# STM32_microcontroller_Power.net
KiCad netlist of a schematic drawn in Altium Designer
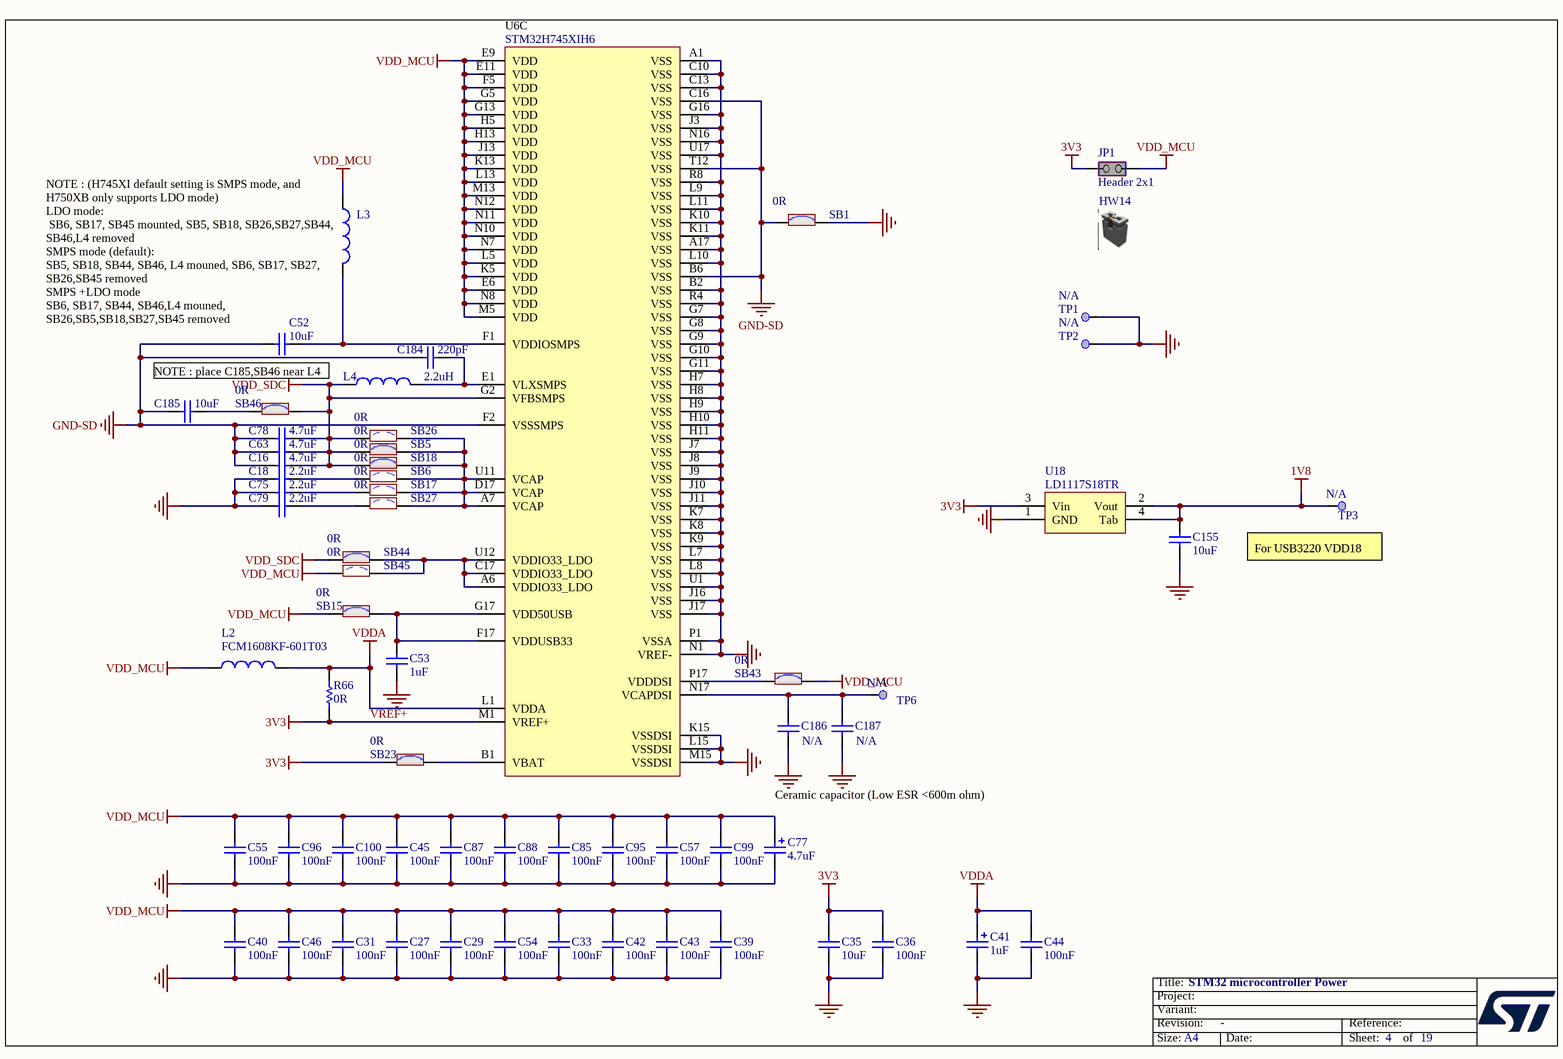
[diagram p0: STM32_microcontroller_Power.SchDoc]

(export (version "E")
  (design (tool "Eeschema 10.0.6"))
  (components
    (comp (ref "C16")
      (value "4.7uF")
      (footprint "C0402")
      (description "Capacitor, MLCC, 4.7uF, 6V3, X5R, 20%, 0402, T=0,5mm")
      (fields
        (field (name "INTERNAL_PART_NUMBER") "MCD-01356")
        (field (name "MANUFACTURER_PART_NUMBER") "GRM155R60J475ME47")
        (field (name "PROVIDED_BY") "Subcon")
      )
      (libsource (lib "MCD_PARTS_database") (part "Capacitor"))
    )
    (comp (ref "C18")
      (value "2.2uF")
      (footprint "C0603")
      (description "Capacitor, MLCC, 2.2uF, 10V, X5R, 10%, 0603, T=0,8mm")
      (fields
        (field (name "INTERNAL_PART_NUMBER") "MCD-00012")
        (field (name "MANUFACTURER_PART_NUMBER") "CC0603KRX5R6BB225")
        (field (name "PROVIDED_BY") "Subcon")
      )
      (libsource (lib "MCD_PARTS_database") (part "Capacitor"))
    )
    (comp (ref "C27")
      (value "100nF")
      (footprint "C0402")
      (description "Capacitor, MLCC, 100nF, 16V, X7R, +/-10%, 0402, T=0.5mm")
      (fields
        (field (name "INTERNAL_PART_NUMBER") "MCD-00006")
        (field (name "MANUFACTURER_PART_NUMBER") "CC0402KRX7R7BB104")
      )
      (libsource (lib "MCD_PARTS_database") (part "Capacitor"))
    )
    (comp (ref "C29")
      (value "100nF")
      (footprint "C0402")
      (description "Capacitor, MLCC, 100nF, 16V, X7R, +/-10%, 0402, T=0.5mm")
      (fields
        (field (name "INTERNAL_PART_NUMBER") "MCD-00006")
        (field (name "MANUFACTURER_PART_NUMBER") "CC0402KRX7R7BB104")
      )
      (libsource (lib "MCD_PARTS_database") (part "Capacitor"))
    )
    (comp (ref "C31")
      (value "100nF")
      (footprint "C0402")
      (description "Capacitor, MLCC, 100nF, 16V, X7R, +/-10%, 0402, T=0.5mm")
      (fields
        (field (name "INTERNAL_PART_NUMBER") "MCD-00006")
        (field (name "MANUFACTURER_PART_NUMBER") "CC0402KRX7R7BB104")
      )
      (libsource (lib "MCD_PARTS_database") (part "Capacitor"))
    )
    (comp (ref "C33")
      (value "100nF")
      (footprint "C0402")
      (description "Capacitor, MLCC, 100nF, 16V, X7R, +/-10%, 0402, T=0.5mm")
      (fields
        (field (name "INTERNAL_PART_NUMBER") "MCD-00006")
        (field (name "MANUFACTURER_PART_NUMBER") "CC0402KRX7R7BB104")
      )
      (libsource (lib "MCD_PARTS_database") (part "Capacitor"))
    )
    (comp (ref "C35")
      (value "10uF")
      (footprint "C0805")
      (description "Capacitor, MLCC, 10uF, 25V, X5R, 10%, 0805, T=0,85mm")
      (fields
        (field (name "INTERNAL_PART_NUMBER") "MCD-00014")
        (field (name "MANUFACTURER_PART_NUMBER") "CC0805KRX5R8BB106")
        (field (name "PROVIDED_BY") "Subcon")
      )
      (libsource (lib "MCD_PARTS_database") (part "Capacitor"))
    )
    (comp (ref "C36")
      (value "100nF")
      (footprint "C0402")
      (description "Capacitor, MLCC, 100nF, 16V, X7R, +/-10%, 0402, T=0.5mm")
      (fields
        (field (name "INTERNAL_PART_NUMBER") "MCD-00006")
        (field (name "MANUFACTURER_PART_NUMBER") "CC0402KRX7R7BB104")
      )
      (libsource (lib "MCD_PARTS_database") (part "Capacitor"))
    )
    (comp (ref "C39")
      (value "100nF")
      (footprint "C0402")
      (description "Capacitor, MLCC, 100nF, 16V, X7R, +/-10%, 0402, T=0.5mm")
      (fields
        (field (name "INTERNAL_PART_NUMBER") "MCD-00006")
        (field (name "MANUFACTURER_PART_NUMBER") "CC0402KRX7R7BB104")
      )
      (libsource (lib "MCD_PARTS_database") (part "Capacitor"))
    )
    (comp (ref "C40")
      (value "100nF")
      (footprint "C0402")
      (description "Capacitor, MLCC, 100nF, 16V, X7R, +/-10%, 0402, T=0.5mm")
      (fields
        (field (name "INTERNAL_PART_NUMBER") "MCD-00006")
        (field (name "MANUFACTURER_PART_NUMBER") "CC0402KRX7R7BB104")
      )
      (libsource (lib "MCD_PARTS_database") (part "Capacitor"))
    )
    (comp (ref "C41")
      (value "1uF")
      (footprint "CPOL_VISHAY_TANTAL-595D_1407_H220")
      (description "Capacitor, Tantalum, 1uF, 35V, +/-10%, 595D case A")
      (fields
        (field (name "INTERNAL_PART_NUMBER") "MCD-00594")
        (field (name "MANUFACTURER_PART_NUMBER") "595D105X9035A2T")
        (field (name "PROVIDED_BY") "Subcon")
      )
      (libsource (lib "MCD_PARTS_database") (part "Cap_POL_TANA"))
    )
    (comp (ref "C42")
      (value "100nF")
      (footprint "C0402")
      (description "Capacitor, MLCC, 100nF, 16V, X7R, +/-10%, 0402, T=0.5mm")
      (fields
        (field (name "INTERNAL_PART_NUMBER") "MCD-00006")
        (field (name "MANUFACTURER_PART_NUMBER") "CC0402KRX7R7BB104")
      )
      (libsource (lib "MCD_PARTS_database") (part "Capacitor"))
    )
    (comp (ref "C43")
      (value "100nF")
      (footprint "C0402")
      (description "Capacitor, MLCC, 100nF, 16V, X7R, +/-10%, 0402, T=0.5mm")
      (fields
        (field (name "INTERNAL_PART_NUMBER") "MCD-00006")
        (field (name "MANUFACTURER_PART_NUMBER") "CC0402KRX7R7BB104")
      )
      (libsource (lib "MCD_PARTS_database") (part "Capacitor"))
    )
    (comp (ref "C44")
      (value "100nF")
      (footprint "C0402")
      (description "Capacitor, MLCC, 100nF, 16V, X7R, +/-10%, 0402, T=0.5mm")
      (fields
        (field (name "INTERNAL_PART_NUMBER") "MCD-00006")
        (field (name "MANUFACTURER_PART_NUMBER") "CC0402KRX7R7BB104")
      )
      (libsource (lib "MCD_PARTS_database") (part "Capacitor"))
    )
    (comp (ref "C45")
      (value "100nF")
      (footprint "C0402")
      (description "Capacitor, MLCC, 100nF, 16V, X7R, +/-10%, 0402, T=0.5mm")
      (fields
        (field (name "INTERNAL_PART_NUMBER") "MCD-00006")
        (field (name "MANUFACTURER_PART_NUMBER") "CC0402KRX7R7BB104")
      )
      (libsource (lib "MCD_PARTS_database") (part "Capacitor"))
    )
    (comp (ref "C46")
      (value "100nF")
      (footprint "C0402")
      (description "Capacitor, MLCC, 100nF, 16V, X7R, +/-10%, 0402, T=0.5mm")
      (fields
        (field (name "INTERNAL_PART_NUMBER") "MCD-00006")
        (field (name "MANUFACTURER_PART_NUMBER") "CC0402KRX7R7BB104")
      )
      (libsource (lib "MCD_PARTS_database") (part "Capacitor"))
    )
    (comp (ref "C52")
      (value "10uF")
      (footprint "C0402")
      (description "Capacitor, MLCC, 10uF, 4V, X5R, 20%, 0402, T=0,5mm")
      (fields
        (field (name "INTERNAL_PART_NUMBER") "MCD-01355")
        (field (name "MANUFACTURER_PART_NUMBER") "GRM155R60G106ME44")
        (field (name "PROVIDED_BY") "Subcon")
      )
      (libsource (lib "MCD_PARTS_database") (part "Capacitor"))
    )
    (comp (ref "C53")
      (value "1uF")
      (footprint "C0603")
      (description "Capacitor, MLCC, 1uF, 16V, X5R, 10%, 0603, T=0,8mm")
      (fields
        (field (name "INTERNAL_PART_NUMBER") "MCD-00010")
        (field (name "MANUFACTURER_PART_NUMBER") "CC0603KRX5R7BB105")
        (field (name "PROVIDED_BY") "Subcon")
      )
      (libsource (lib "MCD_PARTS_database") (part "Capacitor"))
    )
    (comp (ref "C54")
      (value "100nF")
      (footprint "C0402")
      (description "Capacitor, MLCC, 100nF, 16V, X7R, +/-10%, 0402, T=0.5mm")
      (fields
        (field (name "INTERNAL_PART_NUMBER") "MCD-00006")
        (field (name "MANUFACTURER_PART_NUMBER") "CC0402KRX7R7BB104")
      )
      (libsource (lib "MCD_PARTS_database") (part "Capacitor"))
    )
    (comp (ref "C55")
      (value "100nF")
      (footprint "C0402")
      (description "Capacitor, MLCC, 100nF, 16V, X7R, +/-10%, 0402, T=0.5mm")
      (fields
        (field (name "INTERNAL_PART_NUMBER") "MCD-00006")
        (field (name "MANUFACTURER_PART_NUMBER") "CC0402KRX7R7BB104")
      )
      (libsource (lib "MCD_PARTS_database") (part "Capacitor"))
    )
    (comp (ref "C57")
      (value "100nF")
      (footprint "C0402")
      (description "Capacitor, MLCC, 100nF, 16V, X7R, +/-10%, 0402, T=0.5mm")
      (fields
        (field (name "INTERNAL_PART_NUMBER") "MCD-00006")
        (field (name "MANUFACTURER_PART_NUMBER") "CC0402KRX7R7BB104")
      )
      (libsource (lib "MCD_PARTS_database") (part "Capacitor"))
    )
    (comp (ref "C63")
      (value "4.7uF")
      (footprint "C0402")
      (description "Capacitor, MLCC, 4.7uF, 6V3, X5R, 20%, 0402, T=0,5mm")
      (fields
        (field (name "INTERNAL_PART_NUMBER") "MCD-01356")
        (field (name "MANUFACTURER_PART_NUMBER") "GRM155R60J475ME47")
        (field (name "PROVIDED_BY") "Subcon")
      )
      (libsource (lib "MCD_PARTS_database") (part "Capacitor"))
    )
    (comp (ref "C75")
      (value "2.2uF")
      (footprint "C0603")
      (description "Capacitor, MLCC, 2.2uF, 10V, X5R, 10%, 0603, T=0,8mm")
      (fields
        (field (name "INTERNAL_PART_NUMBER") "MCD-00012")
        (field (name "MANUFACTURER_PART_NUMBER") "CC0603KRX5R6BB225")
        (field (name "PROVIDED_BY") "Subcon")
      )
      (libsource (lib "MCD_PARTS_database") (part "Capacitor"))
    )
    (comp (ref "C77")
      (value "4.7uF")
      (footprint "CPOL_VISHAY_TANTAL-595D_1407_H220")
      (description "Capacitor, Tantalum, 4.7uF, 16V, +/-10%, 595D case A")
      (fields
        (field (name "INTERNAL_PART_NUMBER") "MCD-00595")
        (field (name "MANUFACTURER_PART_NUMBER") "595D475X9016A2T")
        (field (name "PROVIDED_BY") "Subcon")
      )
      (libsource (lib "MCD_PARTS_database") (part "Cap_POL_TANA"))
    )
    (comp (ref "C78")
      (value "4.7uF")
      (footprint "C0402")
      (description "Capacitor, MLCC, 4.7uF, 6V3, X5R, 20%, 0402, T=0,5mm")
      (fields
        (field (name "INTERNAL_PART_NUMBER") "MCD-01356")
        (field (name "MANUFACTURER_PART_NUMBER") "GRM155R60J475ME47")
        (field (name "PROVIDED_BY") "Subcon")
      )
      (libsource (lib "MCD_PARTS_database") (part "Capacitor"))
    )
    (comp (ref "C79")
      (value "2.2uF")
      (footprint "C0603")
      (description "Capacitor, MLCC, 2.2uF, 10V, X5R, 10%, 0603, T=0,8mm")
      (fields
        (field (name "INTERNAL_PART_NUMBER") "MCD-00012")
        (field (name "MANUFACTURER_PART_NUMBER") "CC0603KRX5R6BB225")
        (field (name "PROVIDED_BY") "Subcon")
      )
      (libsource (lib "MCD_PARTS_database") (part "Capacitor"))
    )
    (comp (ref "C85")
      (value "100nF")
      (footprint "C0402")
      (description "Capacitor, MLCC, 100nF, 16V, X7R, +/-10%, 0402, T=0.5mm")
      (fields
        (field (name "INTERNAL_PART_NUMBER") "MCD-00006")
        (field (name "MANUFACTURER_PART_NUMBER") "CC0402KRX7R7BB104")
      )
      (libsource (lib "MCD_PARTS_database") (part "Capacitor"))
    )
    (comp (ref "C87")
      (value "100nF")
      (footprint "C0402")
      (description "Capacitor, MLCC, 100nF, 16V, X7R, +/-10%, 0402, T=0.5mm")
      (fields
        (field (name "INTERNAL_PART_NUMBER") "MCD-00006")
        (field (name "MANUFACTURER_PART_NUMBER") "CC0402KRX7R7BB104")
      )
      (libsource (lib "MCD_PARTS_database") (part "Capacitor"))
    )
    (comp (ref "C88")
      (value "100nF")
      (footprint "C0402")
      (description "Capacitor, MLCC, 100nF, 16V, X7R, +/-10%, 0402, T=0.5mm")
      (fields
        (field (name "INTERNAL_PART_NUMBER") "MCD-00006")
        (field (name "MANUFACTURER_PART_NUMBER") "CC0402KRX7R7BB104")
      )
      (libsource (lib "MCD_PARTS_database") (part "Capacitor"))
    )
    (comp (ref "C95")
      (value "100nF")
      (footprint "C0402")
      (description "Capacitor, MLCC, 100nF, 16V, X7R, +/-10%, 0402, T=0.5mm")
      (fields
        (field (name "INTERNAL_PART_NUMBER") "MCD-00006")
        (field (name "MANUFACTURER_PART_NUMBER") "CC0402KRX7R7BB104")
      )
      (libsource (lib "MCD_PARTS_database") (part "Capacitor"))
    )
    (comp (ref "C96")
      (value "100nF")
      (footprint "C0402")
      (description "Capacitor, MLCC, 100nF, 16V, X7R, +/-10%, 0402, T=0.5mm")
      (fields
        (field (name "INTERNAL_PART_NUMBER") "MCD-00006")
        (field (name "MANUFACTURER_PART_NUMBER") "CC0402KRX7R7BB104")
      )
      (libsource (lib "MCD_PARTS_database") (part "Capacitor"))
    )
    (comp (ref "C99")
      (value "100nF")
      (footprint "C0402")
      (description "Capacitor, MLCC, 100nF, 16V, X7R, +/-10%, 0402, T=0.5mm")
      (fields
        (field (name "INTERNAL_PART_NUMBER") "MCD-00006")
        (field (name "MANUFACTURER_PART_NUMBER") "CC0402KRX7R7BB104")
      )
      (libsource (lib "MCD_PARTS_database") (part "Capacitor"))
    )
    (comp (ref "C100")
      (value "100nF")
      (footprint "C0402")
      (description "Capacitor, MLCC, 100nF, 16V, X7R, +/-10%, 0402, T=0.5mm")
      (fields
        (field (name "INTERNAL_PART_NUMBER") "MCD-00006")
        (field (name "MANUFACTURER_PART_NUMBER") "CC0402KRX7R7BB104")
      )
      (libsource (lib "MCD_PARTS_database") (part "Capacitor"))
    )
    (comp (ref "C155")
      (value "10uF")
      (footprint "C0805")
      (description "Capacitor, MLCC, 10uF, 25V, X5R, 10%, 0805, T=0,85mm")
      (fields
        (field (name "INTERNAL_PART_NUMBER") "MCD-00014")
        (field (name "MANUFACTURER_PART_NUMBER") "CC0805KRX5R8BB106")
        (field (name "PROVIDED_BY") "Subcon")
      )
      (libsource (lib "MCD_PARTS_database") (part "Capacitor"))
    )
    (comp (ref "C184")
      (value "220pF")
      (footprint "C0402")
      (description "Capacitor, MLCC, 220pF, 50V, NPO, 5%, 0402, T=0,5mm")
      (fields
        (field (name "INTERNAL_PART_NUMBER") "MCD-01225")
        (field (name "MANUFACTURER_PART_NUMBER") "CC0402JRNPO9BN221")
        (field (name "PROVIDED_BY") "Subcon")
      )
      (libsource (lib "MCD_PARTS_database") (part "Capacitor"))
    )
    (comp (ref "C185")
      (value "10uF")
      (footprint "C0603")
      (description "Capacitor, MLCC, 10uF, 6V3, X5R, 20%, 0603, T=0,8mm")
      (fields
        (field (name "INTERNAL_PART_NUMBER") "MCD-01341")
        (field (name "MANUFACTURER_PART_NUMBER") "GRM188R60J106ME47D")
        (field (name "PROVIDED_BY") "Subcon")
      )
      (libsource (lib "MCD_PARTS_database") (part "Capacitor"))
    )
    (comp (ref "C186")
      (value "N/A")
      (footprint "C0603")
      (description "Capacitor, MLCC, 2.2uF, 10V, X5R, 10%, 0603, T=0,8mm")
      (fields
        (field (name "INTERNAL_PART_NUMBER") "MCD-00012")
        (field (name "MANUFACTURER_PART_NUMBER") "CC0603KRX5R6BB225")
        (field (name "PROVIDED_BY") "Subcon")
      )
      (libsource (lib "MCD_PARTS_database") (part "Capacitor"))
    )
    (comp (ref "C187")
      (value "N/A")
      (footprint "C0402")
      (description "Capacitor, MLCC, 100nF, 16V, X7R, +/-10%, 0402, T=0.5mm")
      (fields
        (field (name "INTERNAL_PART_NUMBER") "MCD-00006")
        (field (name "MANUFACTURER_PART_NUMBER") "CC0402KRX7R7BB104")
      )
      (libsource (lib "MCD_PARTS_database") (part "Capacitor"))
    )
    (comp (ref "HW14")
      (value "Shunt 2.54mm")
      (footprint "N/A")
      (description "SHUNT 2.54mm BLACK")
      (fields
        (field (name "INTERNAL_PART_NUMBER") "MCD-00043")
        (field (name "MANUFACTURER_PART_NUMBER") "SNT-100-BK-G")
        (field (name "PROVIDED_BY") "Subcon")
      )
      (libsource (lib "MCD_PARTS_database") (part "Shunt 2.54mm"))
    )
    (comp (ref "JP1")
      (value "Header 2x1")
      (footprint "CON_SAMTEC_TSW-102-07-G-S")
      (description "Header, 2x1, 2.54mm, VR, TH, T=5.84mm/2.54mm")
      (fields
        (field (name "INTERNAL_PART_NUMBER") "MCD-00683")
        (field (name "MANUFACTURER_PART_NUMBER") "TSW-102-07-G-S")
      )
      (libsource (lib "MCD_PARTS_database") (part "Jumper_Header 2x1 Fitted"))
    )
    (comp (ref "L2")
      (value "BEAD")
      (footprint "L0603")
      (description "Ferrite bead, 600R @1 00MHz, +/-25%, 350mA, 0R5, 0603, T=0.8mm")
      (fields
        (field (name "INTERNAL_PART_NUMBER") "MCD-00047")
        (field (name "MANUFACTURER_PART_NUMBER") "FCM1608KF-601T03")
        (field (name "MANUFACTURER") "TAI-TECH")
      )
      (libsource (lib "MCD_PARTS_database") (part "BEAD"))
    )
    (comp (ref "L3")
      (value "Inductor")
      (footprint "IND_TAIYO-YUDEN_FBMJ1608")
      (description "Ferrite bead, 18R @ 100MHz, +/-30%, 750mA, 0R004, 0603, T=1mm")
      (fields
        (field (name "INTERNAL_PART_NUMBER") "MCD-01431")
        (field (name "MANUFACTURER_PART_NUMBER") "FBMJ1608HM180NTR")
      )
      (libsource (lib "MCD_PARTS_database") (part "Inductor"))
    )
    (comp (ref "L4")
      (value "2.2uH")
      (footprint "IND_2016_MURATA_LQM2MPN2R2NG0")
      (description "Inductor 2.2uH, 2x1.6x0.9mm")
      (fields
        (field (name "INTERNAL_PART_NUMBER") "MCD-01110")
        (field (name "MANUFACTURER_PART_NUMBER") "LQM2MPN2R2NG0")
        (field (name "PROVIDED_BY") "Subcon")
      )
      (libsource (lib "MCD_PARTS_database") (part "Inductor"))
    )
    (comp (ref "R66")
      (value "0R")
      (footprint "R0603")
      (description "Resistor,0R,0603,ULO")
      (fields
        (field (name "INTERNAL_PART_NUMBER") "MCD-00181")
        (field (name "MANUFACTURER_PART_NUMBER") "PMR03EZPJ000")
        (field (name "PROVIDED_BY") "Subcon")
      )
      (libsource (lib "MCD_PARTS_database") (part "Resistor"))
    )
    (comp (ref "SB1")
      (value "0R")
      (footprint "SOLDER-BRIDGE_R0603-0R")
      (description "Solder Bridge ON")
      (fields
        (field (name "INTERNAL_PART_NUMBER") "MCD-00071")
        (field (name "MANUFACTURER") "YAGEO")
        (field (name "PROVIDED_BY") "Subcon")
      )
      (libsource (lib "MCD_PARTS_database") (part "SB_ON"))
    )
    (comp (ref "SB5")
      (value "0R")
      (footprint "SOLDER-BRIDGE_R0603-0R")
      (description "Solder Bridge ON")
      (fields
        (field (name "INTERNAL_PART_NUMBER") "MCD-00071")
        (field (name "MANUFACTURER") "YAGEO")
        (field (name "PROVIDED_BY") "Subcon")
      )
      (libsource (lib "MCD_PARTS_database") (part "SB_ON"))
    )
    (comp (ref "SB6")
      (value "0R")
      (footprint "SOLDER-BRIDGE_R0603-0R")
      (description "Solder Bridge OFF")
      (fields (field (name "INTERNAL_PART_NUMBER") "MCD-00072") (field (name "MANUFACTURER") "YAGEO"))
      (libsource (lib "MCD_PARTS_database") (part "SB_OFF"))
    )
    (comp (ref "SB15")
      (value "0R")
      (footprint "SOLDER-BRIDGE_R0603-0R")
      (description "Solder Bridge ON")
      (fields
        (field (name "INTERNAL_PART_NUMBER") "MCD-00071")
        (field (name "MANUFACTURER") "YAGEO")
        (field (name "PROVIDED_BY") "Subcon")
      )
      (libsource (lib "MCD_PARTS_database") (part "SB_ON"))
    )
    (comp (ref "SB17")
      (value "0R")
      (footprint "SOLDER-BRIDGE_R0603-0R")
      (description "Solder Bridge OFF")
      (fields (field (name "INTERNAL_PART_NUMBER") "MCD-00072") (field (name "MANUFACTURER") "YAGEO"))
      (libsource (lib "MCD_PARTS_database") (part "SB_OFF"))
    )
    (comp (ref "SB18")
      (value "0R")
      (footprint "SOLDER-BRIDGE_R0603-0R")
      (description "Solder Bridge ON")
      (fields
        (field (name "INTERNAL_PART_NUMBER") "MCD-00071")
        (field (name "MANUFACTURER") "YAGEO")
        (field (name "PROVIDED_BY") "Subcon")
      )
      (libsource (lib "MCD_PARTS_database") (part "SB_ON"))
    )
    (comp (ref "SB23")
      (value "0R")
      (footprint "SOLDER-BRIDGE_R0603-0R")
      (description "Solder Bridge ON")
      (fields
        (field (name "INTERNAL_PART_NUMBER") "MCD-00071")
        (field (name "MANUFACTURER") "YAGEO")
        (field (name "PROVIDED_BY") "Subcon")
      )
      (libsource (lib "MCD_PARTS_database") (part "SB_ON"))
    )
    (comp (ref "SB26")
      (value "0R")
      (footprint "SOLDER-BRIDGE_R0603-0R")
      (description "Solder Bridge OFF")
      (fields (field (name "INTERNAL_PART_NUMBER") "MCD-00072") (field (name "MANUFACTURER") "YAGEO"))
      (libsource (lib "MCD_PARTS_database") (part "SB_OFF"))
    )
    (comp (ref "SB27")
      (value "0R")
      (footprint "SOLDER-BRIDGE_R0603-0R")
      (description "Solder Bridge OFF")
      (fields (field (name "INTERNAL_PART_NUMBER") "MCD-00072") (field (name "MANUFACTURER") "YAGEO"))
      (libsource (lib "MCD_PARTS_database") (part "SB_OFF"))
    )
    (comp (ref "SB43")
      (value "0R")
      (footprint "SOLDER-BRIDGE_R0603-0R")
      (description "Solder Bridge ON")
      (fields
        (field (name "INTERNAL_PART_NUMBER") "MCD-00071")
        (field (name "MANUFACTURER") "YAGEO")
        (field (name "PROVIDED_BY") "Subcon")
      )
      (libsource (lib "MCD_PARTS_database") (part "SB_ON"))
    )
    (comp (ref "SB44")
      (value "0R")
      (footprint "SOLDER-BRIDGE_R0603-0R")
      (description "Solder Bridge ON")
      (fields
        (field (name "INTERNAL_PART_NUMBER") "MCD-00071")
        (field (name "MANUFACTURER") "YAGEO")
        (field (name "PROVIDED_BY") "Subcon")
      )
      (libsource (lib "MCD_PARTS_database") (part "SB_ON"))
    )
    (comp (ref "SB45")
      (value "0R")
      (footprint "SOLDER-BRIDGE_R0603-0R")
      (description "Solder Bridge OFF")
      (fields (field (name "INTERNAL_PART_NUMBER") "MCD-00072") (field (name "MANUFACTURER") "YAGEO"))
      (libsource (lib "MCD_PARTS_database") (part "SB_OFF"))
    )
    (comp (ref "SB46")
      (value "0R")
      (footprint "SOLDER-BRIDGE_R0603-0R")
      (description "Solder Bridge ON")
      (fields
        (field (name "INTERNAL_PART_NUMBER") "MCD-00071")
        (field (name "MANUFACTURER") "YAGEO")
        (field (name "PROVIDED_BY") "Subcon")
      )
      (libsource (lib "MCD_PARTS_database") (part "SB_ON"))
    )
    (comp (ref "TP1")
      (value "N/A")
      (footprint "TP_SMD_0-3MM")
      (description "Test Point 0.3mm")
      (fields (field (name "INTERNAL_PART_NUMBER") "MCD-00630") (field (name "Comment") "Test Point"))
      (libsource (lib "MCD_PARTS_database") (part "Test Point"))
    )
    (comp (ref "TP2")
      (value "N/A")
      (footprint "TP_SMD_0-3MM")
      (description "Test Point 0.3mm")
      (fields (field (name "INTERNAL_PART_NUMBER") "MCD-00630") (field (name "Comment") "Test Point"))
      (libsource (lib "MCD_PARTS_database") (part "Test Point"))
    )
    (comp (ref "TP3")
      (value "N/A")
      (footprint "TP_SMD_0-3MM")
      (description "Test Point 0.3mm")
      (fields (field (name "INTERNAL_PART_NUMBER") "MCD-00630") (field (name "Comment") "Test Point"))
      (libsource (lib "") (part "Test Point_1"))
    )
    (comp (ref "TP6")
      (value "N/A")
      (footprint "TP_SMD_0-3MM")
      (description "Test Point 0.3mm")
      (fields (field (name "INTERNAL_PART_NUMBER") "MCD-00630") (field (name "Comment") "Test Point"))
      (libsource (lib "") (part "Test Point_1"))
    )
    (comp (ref "U6")
      (value "STM32H745XIH6")
      (footprint "ICC_TFBGA240+25_14X14_STM32H745H6U_P080")
      (description "32bit MCU TFBGA240+25")
      (fields
        (field (name "INTERNAL_PART_NUMBER") "MCD-01085")
        (field (name "MANUFACTURER") "STMICROELECTRONICS")
        (field (name "PROVIDED_BY") "STM")
      )
      (libsource (lib "MCD_PARTS_database") (part "STM32H745XIH6"))
    )
    (comp (ref "U18")
      (value "LD1117S18TR")
      (footprint "REG_SOT223-TAB")
      (description "Adjustable and fixed low drop positive voltage regulator")
      (fields
        (field (name "INTERNAL_PART_NUMBER") "MCD-01070")
        (field (name "MANUFACTURER") "STMICROELECTRONICS")
        (field (name "PROVIDED_BY") "Subcon")
      )
      (libsource (lib "MCD_PARTS_database") (part "LD1117S18TR"))
    )
  )
  (nets
    (net (code "1") (name "1V8") (class "Default")
      (node (ref "C155") (pin "2") (pinfunction "2_2") (pintype "passive"))
      (node (ref "TP3") (pin "1") (pinfunction "1_1") (pintype "passive"))
      (node (ref "U18") (pin "2") (pinfunction "Vout_2") (pintype "power_in"))
      (node (ref "U18") (pin "4") (pinfunction "Tab_4") (pintype "power_in"))
    )
    (net (code "2") (name "3V3") (class "Default")
      (node (ref "C35") (pin "2") (pinfunction "2_2") (pintype "passive"))
      (node (ref "C36") (pin "2") (pinfunction "2_2") (pintype "passive"))
      (node (ref "JP1") (pin "2") (pinfunction "NO_2") (pintype "passive"))
      (node (ref "R66") (pin "2") (pinfunction "2_2") (pintype "passive"))
      (node (ref "SB23") (pin "1") (pinfunction "1_1") (pintype "passive"))
      (node (ref "U18") (pin "3") (pinfunction "Vin_3") (pintype "power_in"))
      (node (ref "U6") (pin "M1") (pinfunction "VREF+_M1") (pintype "passive"))
    )
    (net (code "3") (name "GND") (class "Default")
      (node (ref "C100") (pin "1") (pinfunction "1_1") (pintype "passive"))
      (node (ref "C155") (pin "1") (pinfunction "1_1") (pintype "passive"))
      (node (ref "C18") (pin "1") (pinfunction "1_1") (pintype "passive"))
      (node (ref "C186") (pin "1") (pinfunction "1_1") (pintype "passive"))
      (node (ref "C187") (pin "1") (pinfunction "1_1") (pintype "passive"))
      (node (ref "C27") (pin "1") (pinfunction "1_1") (pintype "passive"))
      (node (ref "C29") (pin "1") (pinfunction "1_1") (pintype "passive"))
      (node (ref "C31") (pin "1") (pinfunction "1_1") (pintype "passive"))
      (node (ref "C33") (pin "1") (pinfunction "1_1") (pintype "passive"))
      (node (ref "C35") (pin "1") (pinfunction "1_1") (pintype "passive"))
      (node (ref "C36") (pin "1") (pinfunction "1_1") (pintype "passive"))
      (node (ref "C39") (pin "1") (pinfunction "1_1") (pintype "passive"))
      (node (ref "C40") (pin "1") (pinfunction "1_1") (pintype "passive"))
      (node (ref "C41") (pin "2") (pinfunction "2_2") (pintype "passive"))
      (node (ref "C42") (pin "1") (pinfunction "1_1") (pintype "passive"))
      (node (ref "C43") (pin "1") (pinfunction "1_1") (pintype "passive"))
      (node (ref "C44") (pin "1") (pinfunction "1_1") (pintype "passive"))
      (node (ref "C45") (pin "1") (pinfunction "1_1") (pintype "passive"))
      (node (ref "C46") (pin "1") (pinfunction "1_1") (pintype "passive"))
      (node (ref "C53") (pin "1") (pinfunction "1_1") (pintype "passive"))
      (node (ref "C54") (pin "1") (pinfunction "1_1") (pintype "passive"))
      (node (ref "C55") (pin "1") (pinfunction "1_1") (pintype "passive"))
      (node (ref "C57") (pin "1") (pinfunction "1_1") (pintype "passive"))
      (node (ref "C75") (pin "1") (pinfunction "1_1") (pintype "passive"))
      (node (ref "C77") (pin "2") (pinfunction "2_2") (pintype "passive"))
      (node (ref "C79") (pin "1") (pinfunction "1_1") (pintype "passive"))
      (node (ref "C85") (pin "1") (pinfunction "1_1") (pintype "passive"))
      (node (ref "C87") (pin "1") (pinfunction "1_1") (pintype "passive"))
      (node (ref "C88") (pin "1") (pinfunction "1_1") (pintype "passive"))
      (node (ref "C95") (pin "1") (pinfunction "1_1") (pintype "passive"))
      (node (ref "C96") (pin "1") (pinfunction "1_1") (pintype "passive"))
      (node (ref "C99") (pin "1") (pinfunction "1_1") (pintype "passive"))
      (node (ref "SB1") (pin "2") (pinfunction "2_2") (pintype "passive"))
      (node (ref "TP1") (pin "1") (pinfunction "1_1") (pintype "passive"))
      (node (ref "TP2") (pin "1") (pinfunction "1_1") (pintype "passive"))
      (node (ref "U18") (pin "1") (pinfunction "GND_1") (pintype "power_in"))
      (node (ref "U6") (pin "A1") (pinfunction "VSS_A1") (pintype "passive"))
      (node (ref "U6") (pin "A17") (pinfunction "VSS_A17") (pintype "passive"))
      (node (ref "U6") (pin "B2") (pinfunction "VSS_B2") (pintype "passive"))
      (node (ref "U6") (pin "C10") (pinfunction "VSS_C10") (pintype "passive"))
      (node (ref "U6") (pin "C13") (pinfunction "VSS_C13") (pintype "passive"))
      (node (ref "U6") (pin "G10") (pinfunction "VSS_G10") (pintype "passive"))
      (node (ref "U6") (pin "G11") (pinfunction "VSS_G11") (pintype "passive"))
      (node (ref "U6") (pin "G16") (pinfunction "VSS_G16") (pintype "passive"))
      (node (ref "U6") (pin "G7") (pinfunction "VSS_G7") (pintype "passive"))
      (node (ref "U6") (pin "G8") (pinfunction "VSS_G8") (pintype "passive"))
      (node (ref "U6") (pin "G9") (pinfunction "VSS_G9") (pintype "passive"))
      (node (ref "U6") (pin "H10") (pinfunction "VSS_H10") (pintype "passive"))
      (node (ref "U6") (pin "H11") (pinfunction "VSS_H11") (pintype "passive"))
      (node (ref "U6") (pin "H7") (pinfunction "VSS_H7") (pintype "passive"))
      (node (ref "U6") (pin "H8") (pinfunction "VSS_H8") (pintype "passive"))
      (node (ref "U6") (pin "H9") (pinfunction "VSS_H9") (pintype "passive"))
      (node (ref "U6") (pin "J10") (pinfunction "VSS_J10") (pintype "passive"))
      (node (ref "U6") (pin "J11") (pinfunction "VSS_J11") (pintype "passive"))
      (node (ref "U6") (pin "J16") (pinfunction "VSS_J16") (pintype "passive"))
      (node (ref "U6") (pin "J17") (pinfunction "VSS_J17") (pintype "passive"))
      (node (ref "U6") (pin "J3") (pinfunction "VSS_J3") (pintype "passive"))
      (node (ref "U6") (pin "J7") (pinfunction "VSS_J7") (pintype "passive"))
      (node (ref "U6") (pin "J8") (pinfunction "VSS_J8") (pintype "passive"))
      (node (ref "U6") (pin "J9") (pinfunction "VSS_J9") (pintype "passive"))
      (node (ref "U6") (pin "K10") (pinfunction "VSS_K10") (pintype "passive"))
      (node (ref "U6") (pin "K11") (pinfunction "VSS_K11") (pintype "passive"))
      (node (ref "U6") (pin "K15") (pinfunction "VSSDSI_K15") (pintype "passive"))
      (node (ref "U6") (pin "K7") (pinfunction "VSS_K7") (pintype "passive"))
      (node (ref "U6") (pin "K8") (pinfunction "VSS_K8") (pintype "passive"))
      (node (ref "U6") (pin "K9") (pinfunction "VSS_K9") (pintype "passive"))
      (node (ref "U6") (pin "L10") (pinfunction "VSS_L10") (pintype "passive"))
      (node (ref "U6") (pin "L11") (pinfunction "VSS_L11") (pintype "passive"))
      (node (ref "U6") (pin "L15") (pinfunction "VSSDSI_L15") (pintype "passive"))
      (node (ref "U6") (pin "L7") (pinfunction "VSS_L7") (pintype "passive"))
      (node (ref "U6") (pin "L8") (pinfunction "VSS_L8") (pintype "passive"))
      (node (ref "U6") (pin "L9") (pinfunction "VSS_L9") (pintype "passive"))
      (node (ref "U6") (pin "M15") (pinfunction "VSSDSI_M15") (pintype "passive"))
      (node (ref "U6") (pin "N1") (pinfunction "VREF-_N1") (pintype "passive"))
      (node (ref "U6") (pin "N16") (pinfunction "VSS_N16") (pintype "passive"))
      (node (ref "U6") (pin "P1") (pinfunction "VSSA_P1") (pintype "passive"))
      (node (ref "U6") (pin "R4") (pinfunction "VSS_R4") (pintype "passive"))
      (node (ref "U6") (pin "R8") (pinfunction "VSS_R8") (pintype "passive"))
      (node (ref "U6") (pin "U1") (pinfunction "VSS_U1") (pintype "passive"))
      (node (ref "U6") (pin "U17") (pinfunction "VSS_U17") (pintype "passive"))
    )
    (net (code "4") (name "GND-SD") (class "Default")
      (node (ref "C16") (pin "2") (pinfunction "2_2") (pintype "passive"))
      (node (ref "C184") (pin "1") (pinfunction "1_1") (pintype "passive"))
      (node (ref "C185") (pin "1") (pinfunction "1_1") (pintype "passive"))
      (node (ref "C52") (pin "1") (pinfunction "1_1") (pintype "passive"))
      (node (ref "C63") (pin "2") (pinfunction "2_2") (pintype "passive"))
      (node (ref "C78") (pin "2") (pinfunction "2_2") (pintype "passive"))
      (node (ref "SB1") (pin "1") (pinfunction "1_1") (pintype "passive"))
      (node (ref "U6") (pin "B6") (pinfunction "VSS_B6") (pintype "passive"))
      (node (ref "U6") (pin "C16") (pinfunction "VSS_C16") (pintype "passive"))
      (node (ref "U6") (pin "F2") (pinfunction "VSSSMPS_F2") (pintype "passive"))
      (node (ref "U6") (pin "T12") (pinfunction "VSS_T12") (pintype "passive"))
    )
    (net (code "5") (name "Net-(C18-Pad2)") (class "Default")
      (node (ref "C18") (pin "2") (pinfunction "2_2") (pintype "passive"))
      (node (ref "SB6") (pin "1") (pinfunction "1_1") (pintype "passive"))
    )
    (net (code "6") (name "Net-(C75-Pad2)") (class "Default")
      (node (ref "C75") (pin "2") (pinfunction "2_2") (pintype "passive"))
      (node (ref "SB17") (pin "1") (pinfunction "1_1") (pintype "passive"))
    )
    (net (code "7") (name "Net-(C79-Pad2)") (class "Default")
      (node (ref "C79") (pin "2") (pinfunction "2_2") (pintype "passive"))
      (node (ref "SB27") (pin "1") (pinfunction "1_1") (pintype "passive"))
    )
    (net (code "8") (name "Net-(C185-Pad2)") (class "Default")
      (node (ref "C185") (pin "2") (pinfunction "2_2") (pintype "passive"))
      (node (ref "SB46") (pin "1") (pinfunction "1_1") (pintype "passive"))
    )
    (net (code "9") (name "Net-(SB17-Pad2)") (class "Default")
      (node (ref "SB17") (pin "2") (pinfunction "2_2") (pintype "passive"))
      (node (ref "SB18") (pin "2") (pinfunction "2_2") (pintype "passive"))
      (node (ref "SB26") (pin "2") (pinfunction "2_2") (pintype "passive"))
      (node (ref "SB27") (pin "2") (pinfunction "2_2") (pintype "passive"))
      (node (ref "SB5") (pin "2") (pinfunction "2_2") (pintype "passive"))
      (node (ref "SB6") (pin "2") (pinfunction "2_2") (pintype "passive"))
      (node (ref "U6") (pin "A7") (pinfunction "VCAP_A7") (pintype "passive"))
      (node (ref "U6") (pin "D17") (pinfunction "VCAP_D17") (pintype "passive"))
      (node (ref "U6") (pin "U11") (pinfunction "VCAP_U11") (pintype "passive"))
    )
    (net (code "10") (name "Net-(SB44-Pad2)") (class "Default")
      (node (ref "SB44") (pin "2") (pinfunction "2_2") (pintype "passive"))
      (node (ref "SB45") (pin "2") (pinfunction "2_2") (pintype "passive"))
      (node (ref "U6") (pin "A6") (pinfunction "VDDIO33_LDO_A6") (pintype "passive"))
      (node (ref "U6") (pin "C17") (pinfunction "VDDIO33_LDO_C17") (pintype "passive"))
      (node (ref "U6") (pin "U12") (pinfunction "VDDIO33_LDO_U12") (pintype "passive"))
    )
    (net (code "11") (name "Net-(U6C-VBAT)") (class "Default")
      (node (ref "SB23") (pin "2") (pinfunction "2_2") (pintype "passive"))
      (node (ref "U6") (pin "B1") (pinfunction "VBAT_B1") (pintype "passive"))
    )
    (net (code "12") (name "Net-(U6C-VCAPDSI)") (class "Default")
      (node (ref "C186") (pin "2") (pinfunction "2_2") (pintype "passive"))
      (node (ref "C187") (pin "2") (pinfunction "2_2") (pintype "passive"))
      (node (ref "TP6") (pin "1") (pinfunction "1_1") (pintype "passive"))
      (node (ref "U6") (pin "N17") (pinfunction "VCAPDSI_N17") (pintype "passive"))
    )
    (net (code "13") (name "Net-(U6C-VDD50USB)") (class "Default")
      (node (ref "C53") (pin "2") (pinfunction "2_2") (pintype "passive"))
      (node (ref "SB15") (pin "2") (pinfunction "2_2") (pintype "passive"))
      (node (ref "U6") (pin "F17") (pinfunction "VDDUSB33_F17") (pintype "passive"))
      (node (ref "U6") (pin "G17") (pinfunction "VDD50USB_G17") (pintype "passive"))
    )
    (net (code "14") (name "Net-(U6C-VDDDSI)") (class "Default")
      (node (ref "SB43") (pin "1") (pinfunction "1_1") (pintype "passive"))
      (node (ref "U6") (pin "P17") (pinfunction "VDDDSI_P17") (pintype "passive"))
    )
    (net (code "15") (name "Net-(U6C-VDDIOSMPS)") (class "Default")
      (node (ref "C52") (pin "2") (pinfunction "2_2") (pintype "passive"))
      (node (ref "L3") (pin "2") (pinfunction "2_2") (pintype "passive"))
      (node (ref "U6") (pin "F1") (pinfunction "VDDIOSMPS_F1") (pintype "passive"))
    )
    (net (code "16") (name "Net-(U6C-VLXSMPS)") (class "Default")
      (node (ref "C184") (pin "2") (pinfunction "2_2") (pintype "passive"))
      (node (ref "L4") (pin "2") (pinfunction "2_2") (pintype "passive"))
      (node (ref "U6") (pin "E1") (pinfunction "VLXSMPS_E1") (pintype "passive"))
    )
    (net (code "17") (name "VDDA") (class "Default")
      (node (ref "C41") (pin "1") (pinfunction "1_1") (pintype "passive"))
      (node (ref "C44") (pin "2") (pinfunction "2_2") (pintype "passive"))
      (node (ref "L2") (pin "2") (pinfunction "2_2") (pintype "passive"))
      (node (ref "R66") (pin "1") (pinfunction "1_1") (pintype "passive"))
      (node (ref "U6") (pin "L1") (pinfunction "VDDA_L1") (pintype "passive"))
    )
    (net (code "18") (name "VDD_MCU") (class "Default")
      (node (ref "C100") (pin "2") (pinfunction "2_2") (pintype "passive"))
      (node (ref "C27") (pin "2") (pinfunction "2_2") (pintype "passive"))
      (node (ref "C29") (pin "2") (pinfunction "2_2") (pintype "passive"))
      (node (ref "C31") (pin "2") (pinfunction "2_2") (pintype "passive"))
      (node (ref "C33") (pin "2") (pinfunction "2_2") (pintype "passive"))
      (node (ref "C39") (pin "2") (pinfunction "2_2") (pintype "passive"))
      (node (ref "C40") (pin "2") (pinfunction "2_2") (pintype "passive"))
      (node (ref "C42") (pin "2") (pinfunction "2_2") (pintype "passive"))
      (node (ref "C43") (pin "2") (pinfunction "2_2") (pintype "passive"))
      (node (ref "C45") (pin "2") (pinfunction "2_2") (pintype "passive"))
      (node (ref "C46") (pin "2") (pinfunction "2_2") (pintype "passive"))
      (node (ref "C54") (pin "2") (pinfunction "2_2") (pintype "passive"))
      (node (ref "C55") (pin "2") (pinfunction "2_2") (pintype "passive"))
      (node (ref "C57") (pin "2") (pinfunction "2_2") (pintype "passive"))
      (node (ref "C77") (pin "1") (pinfunction "1_1") (pintype "passive"))
      (node (ref "C85") (pin "2") (pinfunction "2_2") (pintype "passive"))
      (node (ref "C87") (pin "2") (pinfunction "2_2") (pintype "passive"))
      (node (ref "C88") (pin "2") (pinfunction "2_2") (pintype "passive"))
      (node (ref "C95") (pin "2") (pinfunction "2_2") (pintype "passive"))
      (node (ref "C96") (pin "2") (pinfunction "2_2") (pintype "passive"))
      (node (ref "C99") (pin "2") (pinfunction "2_2") (pintype "passive"))
      (node (ref "JP1") (pin "1") (pinfunction "COMMON_1") (pintype "passive"))
      (node (ref "L2") (pin "1") (pinfunction "1_1") (pintype "passive"))
      (node (ref "L3") (pin "1") (pinfunction "1_1") (pintype "passive"))
      (node (ref "SB15") (pin "1") (pinfunction "1_1") (pintype "passive"))
      (node (ref "SB43") (pin "2") (pinfunction "2_2") (pintype "passive"))
      (node (ref "SB45") (pin "1") (pinfunction "1_1") (pintype "passive"))
      (node (ref "U6") (pin "E11") (pinfunction "VDD_E11") (pintype "passive"))
      (node (ref "U6") (pin "E6") (pinfunction "VDD_E6") (pintype "passive"))
      (node (ref "U6") (pin "E9") (pinfunction "VDD_E9") (pintype "passive"))
      (node (ref "U6") (pin "F5") (pinfunction "VDD_F5") (pintype "passive"))
      (node (ref "U6") (pin "G13") (pinfunction "VDD_G13") (pintype "passive"))
      (node (ref "U6") (pin "G5") (pinfunction "VDD_G5") (pintype "passive"))
      (node (ref "U6") (pin "H13") (pinfunction "VDD_H13") (pintype "passive"))
      (node (ref "U6") (pin "H5") (pinfunction "VDD_H5") (pintype "passive"))
      (node (ref "U6") (pin "J13") (pinfunction "VDD_J13") (pintype "passive"))
      (node (ref "U6") (pin "K13") (pinfunction "VDD_K13") (pintype "passive"))
      (node (ref "U6") (pin "K5") (pinfunction "VDD_K5") (pintype "passive"))
      (node (ref "U6") (pin "L13") (pinfunction "VDD_L13") (pintype "passive"))
      (node (ref "U6") (pin "L5") (pinfunction "VDD_L5") (pintype "passive"))
      (node (ref "U6") (pin "M13") (pinfunction "VDD_M13") (pintype "passive"))
      (node (ref "U6") (pin "M5") (pinfunction "VDD_M5") (pintype "passive"))
      (node (ref "U6") (pin "N10") (pinfunction "VDD_N10") (pintype "passive"))
      (node (ref "U6") (pin "N11") (pinfunction "VDD_N11") (pintype "passive"))
      (node (ref "U6") (pin "N12") (pinfunction "VDD_N12") (pintype "passive"))
      (node (ref "U6") (pin "N7") (pinfunction "VDD_N7") (pintype "passive"))
      (node (ref "U6") (pin "N8") (pinfunction "VDD_N8") (pintype "passive"))
    )
    (net (code "19") (name "VDD_SDC") (class "Default")
      (node (ref "C16") (pin "1") (pinfunction "1_1") (pintype "passive"))
      (node (ref "C63") (pin "1") (pinfunction "1_1") (pintype "passive"))
      (node (ref "C78") (pin "1") (pinfunction "1_1") (pintype "passive"))
      (node (ref "L4") (pin "1") (pinfunction "1_1") (pintype "passive"))
      (node (ref "SB18") (pin "1") (pinfunction "1_1") (pintype "passive"))
      (node (ref "SB26") (pin "1") (pinfunction "1_1") (pintype "passive"))
      (node (ref "SB44") (pin "1") (pinfunction "1_1") (pintype "passive"))
      (node (ref "SB46") (pin "2") (pinfunction "2_2") (pintype "passive"))
      (node (ref "SB5") (pin "1") (pinfunction "1_1") (pintype "passive"))
      (node (ref "U6") (pin "G2") (pinfunction "VFBSMPS_G2") (pintype "passive"))
    )
  )
)
